# Atmega1284P_New.net
KiCad netlist of a schematic drawn in EAGLE
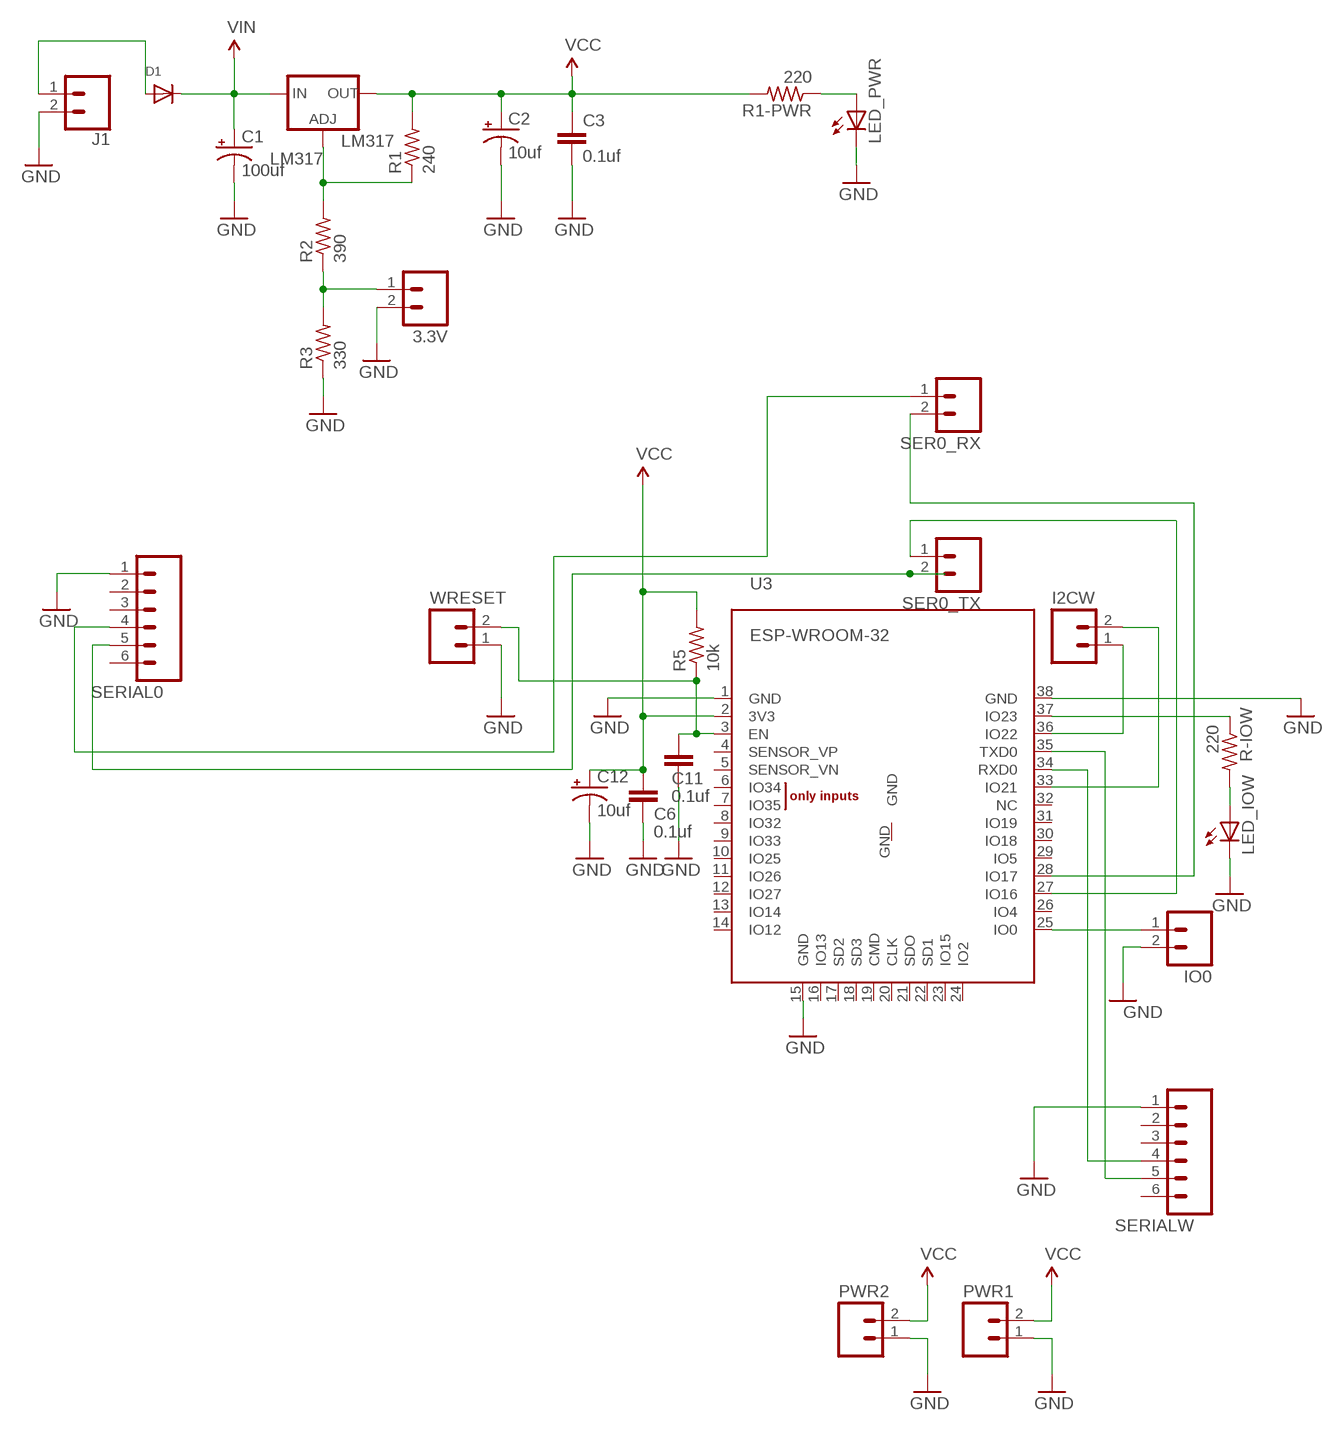
[diagram p0: schematic, sheet 1]

(export (version "E")
  (design (tool "Eeschema 10.0.6"))
  (components
    (comp (ref "3.3V")
      (value "M02PTH")
      (footprint "eagle-import:1X02@1")
      (libsource (lib "eagle-import") (part "M02PTH"))
    )
    (comp (ref "C1")
      (value "100uf")
      (footprint "eagle-import:PANASONIC_D")
      (libsource (lib "eagle-import") (part "CAP_POLD"))
    )
    (comp (ref "C2")
      (value "10uf")
      (footprint "eagle-import:PANASONIC_D")
      (libsource (lib "eagle-import") (part "CAP_POLD"))
    )
    (comp (ref "C3")
      (value "0.1uf")
      (footprint "eagle-import:0805")
      (libsource (lib "eagle-import") (part "CAP0805"))
    )
    (comp (ref "C6")
      (value "0.1uf")
      (footprint "eagle-import:0805")
      (libsource (lib "eagle-import") (part "CAP0805"))
    )
    (comp (ref "C11")
      (value "0.1uf")
      (footprint "eagle-import:0805")
      (libsource (lib "eagle-import") (part "CAP0805"))
    )
    (comp (ref "C12")
      (value "10uf")
      (footprint "eagle-import:PANASONIC_D")
      (libsource (lib "eagle-import") (part "CAP_POLD"))
    )
    (comp (ref "D1")
      (value "DIODE_SOD-123FL")
      (footprint "eagle-import:SOD-123FL")
      (libsource (lib "eagle-import") (part "DIODE_SOD-123FL"))
    )
    (comp (ref "I2CW")
      (value "M02PTH")
      (footprint "eagle-import:1X02@1")
      (libsource (lib "eagle-import") (part "M02PTH"))
    )
    (comp (ref "IO0")
      (value "M02PTH")
      (footprint "eagle-import:1X02@1")
      (libsource (lib "eagle-import") (part "M02PTH"))
    )
    (comp (ref "J1")
      (value "CONN_023.5MM")
      (footprint "eagle-import:SCREWTERMINAL-3.5MM-2")
      (libsource (lib "eagle-import") (part "CONN_023.5MM"))
    )
    (comp (ref "LED_IOW")
      (value "LEDCHIPLED_0805")
      (footprint "eagle-import:CHIPLED_0805")
      (libsource (lib "eagle-import") (part "LEDCHIPLED_0805"))
    )
    (comp (ref "LED_PWR")
      (value "LEDCHIPLED_0805")
      (footprint "eagle-import:CHIPLED_0805")
      (libsource (lib "eagle-import") (part "LEDCHIPLED_0805"))
    )
    (comp (ref "LM317")
      (value "LM317")
      (footprint "eagle-import:SOT223")
      (libsource (lib "eagle-import") (part "V_REG_317SMD"))
    )
    (comp (ref "PWR1")
      (value "M02PTH")
      (footprint "eagle-import:1X02@1")
      (libsource (lib "eagle-import") (part "M02PTH"))
    )
    (comp (ref "PWR2")
      (value "M02PTH")
      (footprint "eagle-import:1X02@1")
      (libsource (lib "eagle-import") (part "M02PTH"))
    )
    (comp (ref "R-IOW")
      (value "220")
      (footprint "eagle-import:R0805")
      (libsource (lib "eagle-import") (part "R-US_R0805"))
    )
    (comp (ref "R1")
      (value "240")
      (footprint "eagle-import:R0805")
      (libsource (lib "eagle-import") (part "R-US_R0805"))
    )
    (comp (ref "R1-PWR")
      (value "220")
      (footprint "eagle-import:R0805")
      (libsource (lib "eagle-import") (part "R-US_R0805"))
    )
    (comp (ref "R2")
      (value "390")
      (footprint "eagle-import:R0805")
      (libsource (lib "eagle-import") (part "R-US_R0805"))
    )
    (comp (ref "R3")
      (value "330")
      (footprint "eagle-import:R0805")
      (libsource (lib "eagle-import") (part "R-US_R0805"))
    )
    (comp (ref "R5")
      (value "10k")
      (footprint "eagle-import:R0805")
      (libsource (lib "eagle-import") (part "R-US_R0805"))
    )
    (comp (ref "SER0_RX")
      (value "M02PTH")
      (footprint "eagle-import:1X02@1")
      (libsource (lib "eagle-import") (part "M02PTH"))
    )
    (comp (ref "SER0_TX")
      (value "M02PTH")
      (footprint "eagle-import:1X02@1")
      (libsource (lib "eagle-import") (part "M02PTH"))
    )
    (comp (ref "SERIAL0")
      (value "M06SILK_FEMALE_PTH")
      (footprint "eagle-import:1X06")
      (libsource (lib "eagle-import") (part "M06SILK_FEMALE_PTH"))
    )
    (comp (ref "SERIALW")
      (value "M06SILK_FEMALE_PTH")
      (footprint "eagle-import:1X06")
      (libsource (lib "eagle-import") (part "M06SILK_FEMALE_PTH"))
    )
    (comp (ref "U3")
      (value "ESP-WROOM-32")
      (footprint "eagle-import:ESP-WROOM-32")
      (libsource (lib "eagle-import") (part "ESP-WROOM-32"))
    )
    (comp (ref "WRESET")
      (value "M02PTH")
      (footprint "eagle-import:1X02@1")
      (libsource (lib "eagle-import") (part "M02PTH"))
    )
  )
  (nets
    (net (code "1") (name "GND") (class "Default")
      (node (ref "3.3V") (pin "2") (pinfunction "2_2") (pintype "passive"))
      (node (ref "C1") (pin "-") (pinfunction "-_-") (pintype "passive"))
      (node (ref "C11") (pin "2") (pinfunction "2_2") (pintype "passive"))
      (node (ref "C12") (pin "-") (pinfunction "-_-") (pintype "passive"))
      (node (ref "C2") (pin "-") (pinfunction "-_-") (pintype "passive"))
      (node (ref "C3") (pin "2") (pinfunction "2_2") (pintype "passive"))
      (node (ref "C6") (pin "2") (pinfunction "2_2") (pintype "passive"))
      (node (ref "IO0") (pin "2") (pinfunction "2_2") (pintype "passive"))
      (node (ref "J1") (pin "2") (pinfunction "2_2") (pintype "passive"))
      (node (ref "LED_IOW") (pin "C") (pinfunction "C_C") (pintype "passive"))
      (node (ref "LED_PWR") (pin "C") (pinfunction "C_C") (pintype "passive"))
      (node (ref "PWR1") (pin "1") (pinfunction "1_1") (pintype "passive"))
      (node (ref "PWR2") (pin "1") (pinfunction "1_1") (pintype "passive"))
      (node (ref "R3") (pin "1") (pinfunction "1_1") (pintype "passive"))
      (node (ref "SERIAL0") (pin "1") (pinfunction "1_1") (pintype "passive"))
      (node (ref "SERIALW") (pin "1") (pinfunction "1_1") (pintype "passive"))
      (node (ref "U3") (pin "1") (pinfunction "GND_1") (pintype "bidirectional"))
      (node (ref "U3") (pin "15") (pinfunction "GND_15") (pintype "bidirectional"))
      (node (ref "U3") (pin "38") (pinfunction "GND_38") (pintype "bidirectional"))
      (node (ref "WRESET") (pin "1") (pinfunction "1_1") (pintype "passive"))
    )
    (net (code "2") (name "Net-(3.3V-Pad1)") (class "Default")
      (node (ref "3.3V") (pin "1") (pinfunction "1_1") (pintype "passive"))
      (node (ref "R2") (pin "1") (pinfunction "1_1") (pintype "passive"))
      (node (ref "R3") (pin "2") (pinfunction "2_2") (pintype "passive"))
    )
    (net (code "3") (name "Net-(D1-PadA)") (class "Default")
      (node (ref "D1") (pin "A") (pinfunction "A_A") (pintype "passive"))
      (node (ref "J1") (pin "1") (pinfunction "1_1") (pintype "passive"))
    )
    (net (code "4") (name "Net-(LED_IOW-PadA)") (class "Default")
      (node (ref "LED_IOW") (pin "A") (pinfunction "A_A") (pintype "passive"))
      (node (ref "R-IOW") (pin "2") (pinfunction "2_2") (pintype "passive"))
    )
    (net (code "5") (name "Net-(LED_PWR-PadA)") (class "Default")
      (node (ref "LED_PWR") (pin "A") (pinfunction "A_A") (pintype "passive"))
      (node (ref "R1-PWR") (pin "1") (pinfunction "1_1") (pintype "passive"))
    )
    (net (code "6") (name "Net-(LM317-ADJ)") (class "Default")
      (node (ref "LM317") (pin "1") (pinfunction "ADJ_1") (pintype "input"))
      (node (ref "R1") (pin "1") (pinfunction "1_1") (pintype "passive"))
      (node (ref "R2") (pin "2") (pinfunction "2_2") (pintype "passive"))
    )
    (net (code "7") (name "Net-(SER0_RX-Pad1)") (class "Default")
      (node (ref "SER0_RX") (pin "1") (pinfunction "1_1") (pintype "passive"))
      (node (ref "SERIAL0") (pin "4") (pinfunction "4_4") (pintype "passive"))
    )
    (net (code "8") (name "Net-(SER0_TX-Pad2)") (class "Default")
      (node (ref "SER0_TX") (pin "2") (pinfunction "2_2") (pintype "passive"))
      (node (ref "SERIAL0") (pin "5") (pinfunction "5_5") (pintype "passive"))
    )
    (net (code "9") (name "Net-(U3-EN)") (class "Default")
      (node (ref "C11") (pin "1") (pinfunction "1_1") (pintype "passive"))
      (node (ref "R5") (pin "1") (pinfunction "1_1") (pintype "passive"))
      (node (ref "U3") (pin "3") (pinfunction "EN_3") (pintype "bidirectional"))
      (node (ref "WRESET") (pin "2") (pinfunction "2_2") (pintype "passive"))
    )
    (net (code "10") (name "Net-(U3-IO0)") (class "Default")
      (node (ref "IO0") (pin "1") (pinfunction "1_1") (pintype "passive"))
      (node (ref "U3") (pin "25") (pinfunction "IO0_25") (pintype "bidirectional"))
    )
    (net (code "11") (name "Net-(U3-IO16)") (class "Default")
      (node (ref "SER0_TX") (pin "1") (pinfunction "1_1") (pintype "passive"))
      (node (ref "U3") (pin "27") (pinfunction "IO16_27") (pintype "bidirectional"))
    )
    (net (code "12") (name "Net-(U3-IO17)") (class "Default")
      (node (ref "SER0_RX") (pin "2") (pinfunction "2_2") (pintype "passive"))
      (node (ref "U3") (pin "28") (pinfunction "IO17_28") (pintype "bidirectional"))
    )
    (net (code "13") (name "Net-(U3-IO21)") (class "Default")
      (node (ref "I2CW") (pin "2") (pinfunction "2_2") (pintype "passive"))
      (node (ref "U3") (pin "33") (pinfunction "IO21_33") (pintype "bidirectional"))
    )
    (net (code "14") (name "Net-(U3-IO22)") (class "Default")
      (node (ref "I2CW") (pin "1") (pinfunction "1_1") (pintype "passive"))
      (node (ref "U3") (pin "36") (pinfunction "IO22_36") (pintype "bidirectional"))
    )
    (net (code "15") (name "Net-(U3-IO23)") (class "Default")
      (node (ref "R-IOW") (pin "1") (pinfunction "1_1") (pintype "passive"))
      (node (ref "U3") (pin "37") (pinfunction "IO23_37") (pintype "bidirectional"))
    )
    (net (code "16") (name "Net-(U3-RXD0)") (class "Default")
      (node (ref "SERIALW") (pin "4") (pinfunction "4_4") (pintype "passive"))
      (node (ref "U3") (pin "34") (pinfunction "RXD0_34") (pintype "bidirectional"))
    )
    (net (code "17") (name "Net-(U3-TXD0)") (class "Default")
      (node (ref "SERIALW") (pin "5") (pinfunction "5_5") (pintype "passive"))
      (node (ref "U3") (pin "35") (pinfunction "TXD0_35") (pintype "bidirectional"))
    )
    (net (code "18") (name "VCC") (class "Default")
      (node (ref "C12") (pin "+") (pinfunction "+_+") (pintype "passive"))
      (node (ref "C2") (pin "+") (pinfunction "+_+") (pintype "passive"))
      (node (ref "C3") (pin "1") (pinfunction "1_1") (pintype "passive"))
      (node (ref "C6") (pin "1") (pinfunction "1_1") (pintype "passive"))
      (node (ref "LM317") (pin "2") (pinfunction "OUT_2") (pintype "output"))
      (node (ref "PWR1") (pin "2") (pinfunction "2_2") (pintype "passive"))
      (node (ref "PWR2") (pin "2") (pinfunction "2_2") (pintype "passive"))
      (node (ref "R1") (pin "2") (pinfunction "2_2") (pintype "passive"))
      (node (ref "R1-PWR") (pin "2") (pinfunction "2_2") (pintype "passive"))
      (node (ref "R5") (pin "2") (pinfunction "2_2") (pintype "passive"))
      (node (ref "U3") (pin "2") (pinfunction "3V3_2") (pintype "bidirectional"))
    )
    (net (code "19") (name "VIN") (class "Default")
      (node (ref "C1") (pin "+") (pinfunction "+_+") (pintype "passive"))
      (node (ref "D1") (pin "C") (pinfunction "C_C") (pintype "passive"))
      (node (ref "LM317") (pin "3") (pinfunction "IN_3") (pintype "input"))
    )
    (net (code "20") (name "unconnected-(SERIAL0-Pad2)") (class "Default")
      (node (ref "SERIAL0") (pin "2") (pinfunction "2_2") (pintype "passive"))
    )
    (net (code "21") (name "unconnected-(SERIAL0-Pad3)") (class "Default")
      (node (ref "SERIAL0") (pin "3") (pinfunction "3_3") (pintype "passive"))
    )
    (net (code "22") (name "unconnected-(SERIAL0-Pad6)") (class "Default")
      (node (ref "SERIAL0") (pin "6") (pinfunction "6_6") (pintype "passive"))
    )
    (net (code "23") (name "unconnected-(SERIALW-Pad2)") (class "Default")
      (node (ref "SERIALW") (pin "2") (pinfunction "2_2") (pintype "passive"))
    )
    (net (code "24") (name "unconnected-(SERIALW-Pad3)") (class "Default")
      (node (ref "SERIALW") (pin "3") (pinfunction "3_3") (pintype "passive"))
    )
    (net (code "25") (name "unconnected-(SERIALW-Pad6)") (class "Default")
      (node (ref "SERIALW") (pin "6") (pinfunction "6_6") (pintype "passive"))
    )
    (net (code "26") (name "unconnected-(U3-CLK-Pad20)") (class "Default")
      (node (ref "U3") (pin "20") (pinfunction "CLK_20") (pintype "bidirectional"))
    )
    (net (code "27") (name "unconnected-(U3-CMD-Pad19)") (class "Default")
      (node (ref "U3") (pin "19") (pinfunction "CMD_19") (pintype "bidirectional"))
    )
    (net (code "28") (name "unconnected-(U3-IO2-Pad24)") (class "Default")
      (node (ref "U3") (pin "24") (pinfunction "IO2_24") (pintype "bidirectional"))
    )
    (net (code "29") (name "unconnected-(U3-IO4-Pad26)") (class "Default")
      (node (ref "U3") (pin "26") (pinfunction "IO4_26") (pintype "bidirectional"))
    )
    (net (code "30") (name "unconnected-(U3-IO5-Pad29)") (class "Default")
      (node (ref "U3") (pin "29") (pinfunction "IO5_29") (pintype "bidirectional"))
    )
    (net (code "31") (name "unconnected-(U3-IO12-Pad14)") (class "Default")
      (node (ref "U3") (pin "14") (pinfunction "IO12_14") (pintype "bidirectional"))
    )
    (net (code "32") (name "unconnected-(U3-IO13-Pad16)") (class "Default")
      (node (ref "U3") (pin "16") (pinfunction "IO13_16") (pintype "bidirectional"))
    )
    (net (code "33") (name "unconnected-(U3-IO14-Pad13)") (class "Default")
      (node (ref "U3") (pin "13") (pinfunction "IO14_13") (pintype "bidirectional"))
    )
    (net (code "34") (name "unconnected-(U3-IO15-Pad23)") (class "Default")
      (node (ref "U3") (pin "23") (pinfunction "IO15_23") (pintype "bidirectional"))
    )
    (net (code "35") (name "unconnected-(U3-IO18-Pad30)") (class "Default")
      (node (ref "U3") (pin "30") (pinfunction "IO18_30") (pintype "bidirectional"))
    )
    (net (code "36") (name "unconnected-(U3-IO19-Pad31)") (class "Default")
      (node (ref "U3") (pin "31") (pinfunction "IO19_31") (pintype "bidirectional"))
    )
    (net (code "37") (name "unconnected-(U3-IO25-Pad10)") (class "Default")
      (node (ref "U3") (pin "10") (pinfunction "IO25_10") (pintype "bidirectional"))
    )
    (net (code "38") (name "unconnected-(U3-IO26-Pad11)") (class "Default")
      (node (ref "U3") (pin "11") (pinfunction "IO26_11") (pintype "bidirectional"))
    )
    (net (code "39") (name "unconnected-(U3-IO27-Pad12)") (class "Default")
      (node (ref "U3") (pin "12") (pinfunction "IO27_12") (pintype "bidirectional"))
    )
    (net (code "40") (name "unconnected-(U3-IO32-Pad8)") (class "Default")
      (node (ref "U3") (pin "8") (pinfunction "IO32_8") (pintype "bidirectional"))
    )
    (net (code "41") (name "unconnected-(U3-IO33-Pad9)") (class "Default")
      (node (ref "U3") (pin "9") (pinfunction "IO33_9") (pintype "bidirectional"))
    )
    (net (code "42") (name "unconnected-(U3-IO34-Pad6)") (class "Default")
      (node (ref "U3") (pin "6") (pinfunction "IO34_6") (pintype "input"))
    )
    (net (code "43") (name "unconnected-(U3-IO35-Pad7)") (class "Default")
      (node (ref "U3") (pin "7") (pinfunction "IO35_7") (pintype "input"))
    )
    (net (code "44") (name "unconnected-(U3-NC-Pad32)") (class "Default")
      (node (ref "U3") (pin "32") (pinfunction "NC_32") (pintype "bidirectional"))
    )
    (net (code "45") (name "unconnected-(U3-PadGND)") (class "Default")
      (node (ref "U3") (pin "GND") (pinfunction "GND_GND") (pintype "bidirectional"))
    )
    (net (code "46") (name "unconnected-(U3-SD1-Pad22)") (class "Default")
      (node (ref "U3") (pin "22") (pinfunction "SD1_22") (pintype "bidirectional"))
    )
    (net (code "47") (name "unconnected-(U3-SD2-Pad17)") (class "Default")
      (node (ref "U3") (pin "17") (pinfunction "SD2_17") (pintype "bidirectional"))
    )
    (net (code "48") (name "unconnected-(U3-SD3-Pad18)") (class "Default")
      (node (ref "U3") (pin "18") (pinfunction "SD3_18") (pintype "bidirectional"))
    )
    (net (code "49") (name "unconnected-(U3-SDO-Pad21)") (class "Default")
      (node (ref "U3") (pin "21") (pinfunction "SDO_21") (pintype "bidirectional"))
    )
    (net (code "50") (name "unconnected-(U3-SENSOR_VN-Pad5)") (class "Default")
      (node (ref "U3") (pin "5") (pinfunction "SENSOR_VN_5") (pintype "input"))
    )
    (net (code "51") (name "unconnected-(U3-SENSOR_VP-Pad4)") (class "Default")
      (node (ref "U3") (pin "4") (pinfunction "SENSOR_VP_4") (pintype "input"))
    )
  )
)
